# comm_connector.net
KiCad netlist of a schematic drawn in Altium Designer
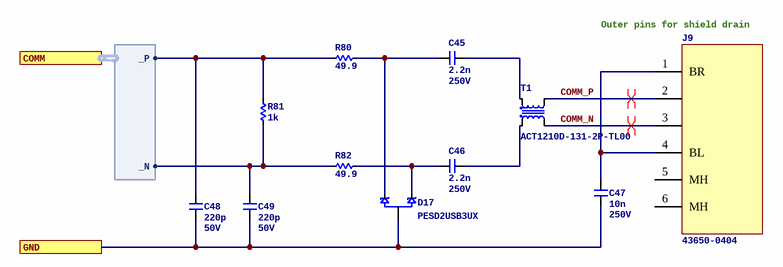
[diagram p0: comm_connector.SchDoc]

(export (version "E")
  (design (tool "Eeschema 10.0.6"))
  (components
    (comp (ref "C45")
      (value "CGA4J3C0G2E222JT0Y0N")
      (footprint "C0805")
      (fields
        (field (name "CAPACITANCE") "2.2n")
        (field (name "MANUFACTURER") "TDK")
        (field (name "VOLTAGE RATING") "250V")
      )
      (libsource (lib "database") (part "__template_cap"))
    )
    (comp (ref "C46")
      (value "CGA4J3C0G2E222JT0Y0N")
      (footprint "C0805")
      (fields
        (field (name "CAPACITANCE") "2.2n")
        (field (name "MANUFACTURER") "TDK")
        (field (name "VOLTAGE RATING") "250V")
      )
      (libsource (lib "database") (part "__template_cap"))
    )
    (comp (ref "C47")
      (value "CC0805KKX7RYBB103")
      (footprint "C0805")
      (fields
        (field (name "CAPACITANCE") "10n")
        (field (name "MANUFACTURER") "YAGEO")
        (field (name "VOLTAGE RATING") "250V")
      )
      (libsource (lib "database") (part "__template_cap"))
    )
    (comp (ref "C48")
      (value "GRM1555C1H221JA01D")
      (footprint "C0402")
      (fields
        (field (name "CAPACITANCE") "220p")
        (field (name "MANUFACTURER") "Murata Electronics")
        (field (name "VOLTAGE RATING") "50V")
      )
      (libsource (lib "database") (part "__template_cap"))
    )
    (comp (ref "C49")
      (value "GRM1555C1H221JA01D")
      (footprint "C0402")
      (fields
        (field (name "CAPACITANCE") "220p")
        (field (name "MANUFACTURER") "Murata Electronics")
        (field (name "VOLTAGE RATING") "50V")
      )
      (libsource (lib "database") (part "__template_cap"))
    )
    (comp (ref "D17")
      (value "PESD2USB3UX")
      (footprint "3SOT23")
      (description "DIODE ESD USB SOT-23")
      (fields (field (name "MANUFACTURER") "Nexperia USA Inc."))
      (libsource (lib "SSCP") (part "TVS_PESD2USB3UX-T"))
    )
    (comp (ref "J9")
      (value "43650-0404")
      (footprint "MOLEX_MICROFIT_0436500404")
      (description "Conn Wire to Board HDR 4 POS 3mm Solder RA Thru-Hole 4 Terminal 1 Port Micro-Fit 3.0")
      (fields (field (name "MANUFACTURER") "Molex"))
      (libsource (lib "SSCP") (part "CONN_MOLEX_MICROFIT_4POS_RA_43650-0404"))
    )
    (comp (ref "R80")
      (value "49.9")
      (footprint "R0402")
      (fields
        (field (name "MANUFACTURER PART NUMBER") "0402WGF499JTCE")
        (field (name "MANUFACTURER") "UNI-ROYAL(Uniroyal Elec)")
        (field (name "TOLERANCE") "1%")
      )
      (libsource (lib "database") (part "__template_resistor"))
    )
    (comp (ref "R81")
      (value "1k")
      (footprint "R0603")
      (fields
        (field (name "MANUFACTURER PART NUMBER") "HP03W5F1001T5E")
        (field (name "MANUFACTURER") "UNI-ROYAL(Uniroyal Elec)")
        (field (name "TOLERANCE") "1%")
      )
      (libsource (lib "database") (part "__template_resistor"))
    )
    (comp (ref "R82")
      (value "49.9")
      (footprint "R0402")
      (fields
        (field (name "MANUFACTURER PART NUMBER") "0402WGF499JTCE")
        (field (name "MANUFACTURER") "UNI-ROYAL(Uniroyal Elec)")
        (field (name "TOLERANCE") "1%")
      )
      (libsource (lib "database") (part "__template_resistor"))
    )
    (comp (ref "T1")
      (value "ACT1210D-131-2P-TL00")
      (footprint "CHOKE_ACT1210D-131-2P-TL00")
      (description "130 µH @ 100 kHz 2 Line Common Mode Choke Surface Mount 6.7 kOhms @ 10 MHz 115mA DCR 3.5Ohm")
      (fields (field (name "MANUFACTURER") "TDK Corporation"))
      (libsource (lib "SSCP") (part "CHOKE_ACT1210D-131-2P-TL00"))
    )
  )
  (nets
    (net (code "2") (name "/COMM_N") (class "Default")
      (node (ref "J9") (pin "3") (pintype "passive"))
      (node (ref "T1") (pin "3") (pintype "passive"))
    )
    (net (code "3") (name "/COMM_P") (class "Default")
      (node (ref "J9") (pin "2") (pintype "passive"))
      (node (ref "T1") (pin "4") (pintype "passive"))
    )
    (net (code "4") (name "/GND") (class "Default")
      (node (ref "C47") (pin "2") (pintype "passive"))
      (node (ref "C48") (pin "2") (pintype "passive"))
      (node (ref "C49") (pin "2") (pintype "passive"))
      (node (ref "D17") (pin "3") (pintype "passive"))
    )
    (net (code "6") (name "Net-(C45-Pad1)") (class "Default")
      (node (ref "C45") (pin "1") (pintype "passive"))
      (node (ref "D17") (pin "2") (pintype "passive"))
      (node (ref "R80") (pin "2") (pintype "passive"))
    )
    (net (code "7") (name "Net-(C45-Pad2)") (class "Default")
      (node (ref "C45") (pin "2") (pintype "passive"))
      (node (ref "T1") (pin "1") (pintype "passive"))
    )
    (net (code "8") (name "Net-(C46-Pad1)") (class "Default")
      (node (ref "C46") (pin "1") (pintype "passive"))
      (node (ref "D17") (pin "1") (pintype "passive"))
      (node (ref "R82") (pin "2") (pintype "passive"))
    )
    (net (code "9") (name "Net-(C46-Pad2)") (class "Default")
      (node (ref "C46") (pin "2") (pintype "passive"))
      (node (ref "T1") (pin "2") (pintype "passive"))
    )
    (net (code "10") (name "Net-(C48-Pad1)") (class "Default")
      (node (ref "C48") (pin "1") (pintype "passive"))
      (node (ref "R80") (pin "1") (pintype "passive"))
      (node (ref "R81") (pin "2") (pintype "passive"))
    )
    (net (code "11") (name "Net-(C49-Pad1)") (class "Default")
      (node (ref "C49") (pin "1") (pintype "passive"))
      (node (ref "R81") (pin "1") (pintype "passive"))
      (node (ref "R82") (pin "1") (pintype "passive"))
    )
    (net (code "12") (name "Net-(J9-BL)") (class "Default")
      (node (ref "C47") (pin "1") (pintype "passive"))
      (node (ref "J9") (pin "1") (pinfunction "BR_1") (pintype "passive"))
      (node (ref "J9") (pin "4") (pinfunction "BL_4") (pintype "passive"))
    )
    (net (code "13") (name "unconnected-(J9-MH-Pad5)") (class "Default")
      (node (ref "J9") (pin "5") (pinfunction "MH_5") (pintype "passive"))
    )
    (net (code "14") (name "unconnected-(J9-MH-Pad6)") (class "Default")
      (node (ref "J9") (pin "6") (pinfunction "MH_6") (pintype "passive"))
    )
  )
)
